# Backlight_Control.net
KiCad netlist of a schematic drawn in Altium Designer
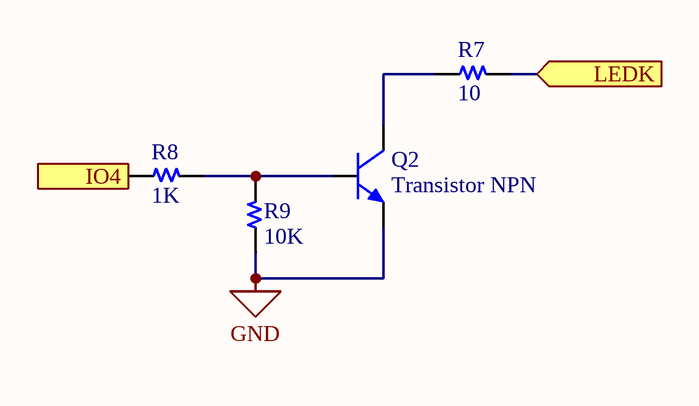
[diagram p0: Backlight Control.SchDoc]

(export (version "E")
  (design (tool "Eeschema 10.0.6"))
  (components
    (comp (ref "Q2")
      (value "Transistor NPN")
      (footprint "SOT-23")
      (description "NPN Bipolar Transistor")
      (libsource (lib "chipfc_libs") (part "Transistor NPN"))
    )
    (comp (ref "R7")
      (value "10")
      (footprint "R 0805")
      (description "Resistor")
      (libsource (lib "chipfc_libs") (part "Resistor"))
    )
    (comp (ref "R8")
      (value "1K")
      (footprint "R 0805")
      (description "Resistor")
      (libsource (lib "chipfc_libs") (part "Resistor"))
    )
    (comp (ref "R9")
      (value "10K")
      (footprint "R 0805")
      (description "Resistor")
      (libsource (lib "chipfc_libs") (part "Resistor"))
    )
  )
  (nets
    (net (code "1") (name "/IO4") (class "Default")
      (node (ref "R8") (pin "1") (pinfunction "1_1") (pintype "passive"))
    )
    (net (code "2") (name "/LEDK") (class "Default")
      (node (ref "R7") (pin "2") (pinfunction "2_2") (pintype "passive"))
    )
    (net (code "3") (name "GND") (class "Default")
      (node (ref "Q2") (pin "2") (pinfunction "E_2") (pintype "passive"))
      (node (ref "R9") (pin "1") (pinfunction "1_1") (pintype "passive"))
    )
    (net (code "4") (name "Net-(Q2-B)") (class "Default")
      (node (ref "Q2") (pin "1") (pinfunction "B_1") (pintype "passive"))
      (node (ref "R8") (pin "2") (pinfunction "2_2") (pintype "passive"))
      (node (ref "R9") (pin "2") (pinfunction "2_2") (pintype "passive"))
    )
    (net (code "5") (name "Net-(Q2-C)") (class "Default")
      (node (ref "Q2") (pin "3") (pinfunction "C_3") (pintype "passive"))
      (node (ref "R7") (pin "1") (pinfunction "1_1") (pintype "passive"))
    )
  )
)
